# Esquematico.net
KiCad netlist of a schematic drawn in Altium Designer
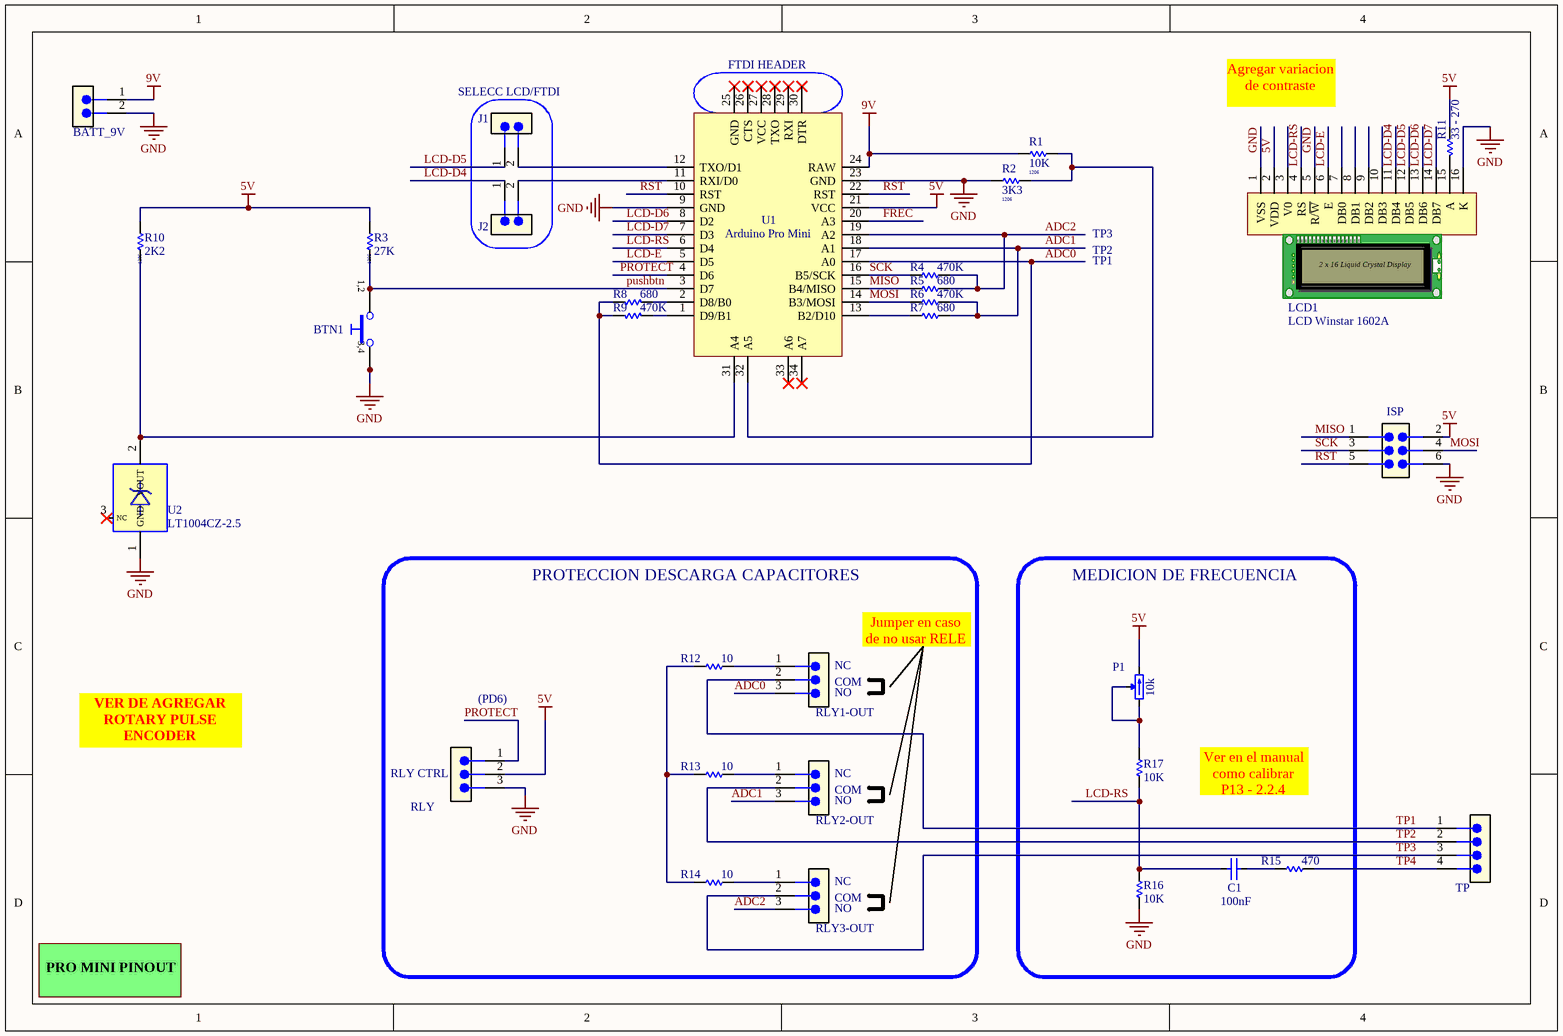
[diagram p0: Esquematico.SchDoc]

(export (version "E")
  (design (tool "Eeschema 10.0.6"))
  (components
    (comp (ref "BATT_9V")
      (value "M20-9 73 02 46")
      (footprint "HEADER2X1")
      (description "Header recto M 100 mils pitch 2x1")
      (fields (field (name "EM_MFR_PARTNUM") "NA") (field (name "MANUFACTURER") "Harwin"))
      (libsource (lib "") (part "HEADER 2X1_1"))
    )
    (comp (ref "BTN1")
      (value "Push Button")
      (footprint "PB_OMRON_B3F-1070")
      (description "Push-Button Switch SPDT")
      (fields
        (field (name "PART NUMBER") "PB_OMRON_B3F-1070")
        (field (name "MANUFACTURER") "OMRON")
        (field (name "AUTHOR") "CERN DEM JLC")
      )
      (libsource (lib "Schlib1") (part "SW TACT LONG 4Pin"))
    )
    (comp (ref "C1") (value "100nF") (footprint "1206 - CAP") (libsource (lib "Schlib1") (part "CAP_1206")))
    (comp (ref "ISP")
      (value "M20-9 72 03 46")
      (footprint "HEADER3X2")
      (description "Header recto M 100 mils pitch 3x2")
      (fields (field (name "EM_MFR_PARTNUM") "NA") (field (name "MANUFACTURER") "Harwin"))
      (libsource (lib "Schlib1") (part "HEADER 3X2"))
    )
    (comp (ref "J1")
      (value "M20-9 73 02 46")
      (footprint "HEADER2X1")
      (description "Header recto M 100 mils pitch 2x1")
      (fields (field (name "EM_MFR_PARTNUM") "NA") (field (name "MANUFACTURER") "Harwin"))
      (libsource (lib "") (part "HEADER 2X1_2"))
    )
    (comp (ref "J2")
      (value "M20-9 73 02 46")
      (footprint "HEADER2X1")
      (description "Header recto M 100 mils pitch 2x1")
      (fields (field (name "EM_MFR_PARTNUM") "NA") (field (name "MANUFACTURER") "Harwin"))
      (libsource (lib "Schlib1") (part "HEADER 2X1"))
    )
    (comp (ref "LCD1")
      (value "LCD Winstar 1602A")
      (footprint "LCD_1602A")
      (description "16x2 4-Bit Parallel LCD display HD44780 compatible")
      (libsource (lib "Schlib1") (part "LCD Winstar 1602A"))
    )
    (comp (ref "P1")
      (value "10k")
      (footprint "TRIM_BOURNS_3266W")
      (description "Trimming Pot THD")
      (fields
        (field (name "PART NUMBER") "TRIM_12T_10K_BOURNS_3266W-1-103LF")
        (field (name "POWER") "0.25W")
        (field (name "AUTHOR") "CERN DEM JLC")
      )
      (libsource (lib "Schlib1") (part "Trimming Pot THD"))
    )
    (comp (ref "R1")
      (value "10K")
      (footprint "1206 - RES")
      (fields (field (name "PACKAGE") "1206"))
      (libsource (lib "Schlib1") (part "RES_1206"))
    )
    (comp (ref "R2")
      (value "3K3")
      (footprint "1206 - RES")
      (fields (field (name "PACKAGE") "1206"))
      (libsource (lib "Schlib1") (part "RES_1206"))
    )
    (comp (ref "R3")
      (value "27K")
      (footprint "1206 - RES")
      (fields (field (name "PACKAGE") "1206"))
      (libsource (lib "Schlib1") (part "RES_1206"))
    )
    (comp (ref "R4") (value "470K") (footprint "1206 - RES") (libsource (lib "Schlib1") (part "RES_1206")))
    (comp (ref "R5") (value "680") (footprint "1206 - RES") (libsource (lib "Schlib1") (part "RES_1206")))
    (comp (ref "R6") (value "470K") (footprint "1206 - RES") (libsource (lib "Schlib1") (part "RES_1206")))
    (comp (ref "R7") (value "680") (footprint "1206 - RES") (libsource (lib "Schlib1") (part "RES_1206")))
    (comp (ref "R8") (value "680") (footprint "1206 - RES") (libsource (lib "Schlib1") (part "RES_1206")))
    (comp (ref "R9") (value "470K") (footprint "1206 - RES") (libsource (lib "Schlib1") (part "RES_1206")))
    (comp (ref "R10")
      (value "2K2")
      (footprint "1206 - RES")
      (fields (field (name "PACKAGE") "1206"))
      (libsource (lib "Schlib1") (part "RES_1206"))
    )
    (comp (ref "R11")
      (value "33 - 270")
      (footprint "1206 - RES")
      (libsource (lib "Schlib1") (part "RES_1206"))
    )
    (comp (ref "R12") (value "10") (footprint "1206 - RES") (libsource (lib "Schlib1") (part "RES_1206")))
    (comp (ref "R13") (value "10") (footprint "1206 - RES") (libsource (lib "Schlib1") (part "RES_1206")))
    (comp (ref "R14") (value "10") (footprint "1206 - RES") (libsource (lib "Schlib1") (part "RES_1206")))
    (comp (ref "R15") (value "470") (footprint "1206 - RES") (libsource (lib "Schlib1") (part "RES_1206")))
    (comp (ref "R16") (value "10K") (footprint "1206 - RES") (libsource (lib "Schlib1") (part "RES_1206")))
    (comp (ref "R17") (value "10K") (footprint "1206 - RES") (libsource (lib "Schlib1") (part "RES_1206")))
    (comp (ref "RLY") (value "HEADER 3X1") (footprint "HEADER3X1") (libsource (lib "") (part "HEADER 3X1_1")))
    (comp (ref "RLY1-OUT")
      (value "HEADER 3X1")
      (footprint "HEADER3X1")
      (libsource (lib "Schlib1") (part "HEADER 3X1"))
    )
    (comp (ref "RLY2-OUT")
      (value "HEADER 3X1")
      (footprint "HEADER3X1")
      (libsource (lib "Schlib1") (part "HEADER 3X1"))
    )
    (comp (ref "RLY3-OUT")
      (value "HEADER 3X1")
      (footprint "HEADER3X1")
      (libsource (lib "Schlib1") (part "HEADER 3X1"))
    )
    (comp (ref "TP")
      (value "M20-9 73 04 46")
      (footprint "HEADER4X1")
      (description "Header recto M 100 mils pitch 4x1")
      (fields (field (name "EM_MFR_PARTNUM") "NA") (field (name "MANUFACTURER") "Harwin"))
      (libsource (lib "Schlib1") (part "HEADER 4X1"))
    )
    (comp (ref "U1")
      (value "Arduino Pro Mini")
      (footprint "Arduino Pro Mini")
      (libsource (lib "Schlib1") (part "Arduino Pro Mini"))
    )
    (comp (ref "U2")
      (value "LT1004CZ-2.5")
      (footprint "TO-92")
      (description "VREF SHUNT 2.5V TO-92")
      (fields (field (name "MANUFACTURER") "Analog Devices"))
      (libsource (lib "Schlib1") (part "LT1004CZ-2.5"))
    )
  )
  (nets
    (net (code "1") (name "/ADC0") (class "Default")
      (node (ref "R8") (pin "1") (pinfunction "1_1") (pintype "passive"))
      (node (ref "R9") (pin "1") (pinfunction "1_1") (pintype "passive"))
      (node (ref "RLY1-OUT") (pin "3") (pinfunction "3_3") (pintype "passive"))
      (node (ref "U1") (pin "17") (pinfunction "A0_17") (pintype "passive"))
    )
    (net (code "2") (name "/ADC1") (class "Default")
      (node (ref "R6") (pin "1") (pinfunction "1_1") (pintype "passive"))
      (node (ref "R7") (pin "1") (pinfunction "1_1") (pintype "passive"))
      (node (ref "RLY2-OUT") (pin "3") (pinfunction "3_3") (pintype "passive"))
      (node (ref "U1") (pin "18") (pinfunction "A1_18") (pintype "passive"))
    )
    (net (code "3") (name "/ADC2") (class "Default")
      (node (ref "R4") (pin "1") (pinfunction "1_1") (pintype "passive"))
      (node (ref "R5") (pin "1") (pinfunction "1_1") (pintype "passive"))
      (node (ref "RLY3-OUT") (pin "3") (pinfunction "3_3") (pintype "passive"))
      (node (ref "U1") (pin "19") (pinfunction "A2_19") (pintype "passive"))
    )
    (net (code "4") (name "/FREC") (class "Default")
      (node (ref "U1") (pin "20") (pinfunction "A3_20") (pintype "passive"))
    )
    (net (code "5") (name "/LCD-D4") (class "Default")
      (node (ref "J2") (pin "1") (pinfunction "1_1") (pintype "passive"))
      (node (ref "LCD1") (pin "11") (pinfunction "DB4_11") (pintype "passive"))
    )
    (net (code "6") (name "/LCD-D5") (class "Default")
      (node (ref "J1") (pin "1") (pinfunction "1_1") (pintype "passive"))
      (node (ref "LCD1") (pin "12") (pinfunction "DB5_12") (pintype "passive"))
    )
    (net (code "7") (name "/LCD-D6") (class "Default")
      (node (ref "LCD1") (pin "13") (pinfunction "DB6_13") (pintype "passive"))
      (node (ref "U1") (pin "8") (pinfunction "D2_8") (pintype "passive"))
    )
    (net (code "8") (name "/LCD-D7") (class "Default")
      (node (ref "LCD1") (pin "14") (pinfunction "DB7_14") (pintype "passive"))
      (node (ref "U1") (pin "7") (pinfunction "D3_7") (pintype "passive"))
    )
    (net (code "9") (name "/LCD-E") (class "Default")
      (node (ref "LCD1") (pin "6") (pinfunction "E_6") (pintype "passive"))
      (node (ref "U1") (pin "5") (pinfunction "D5_5") (pintype "passive"))
    )
    (net (code "10") (name "/LCD-RS") (class "Default")
      (node (ref "C1") (pin "1") (pinfunction "1_1") (pintype "passive"))
      (node (ref "LCD1") (pin "4") (pinfunction "RS_4") (pintype "passive"))
      (node (ref "R16") (pin "2") (pinfunction "2_2") (pintype "passive"))
      (node (ref "R17") (pin "1") (pinfunction "1_1") (pintype "passive"))
      (node (ref "U1") (pin "6") (pinfunction "D4_6") (pintype "passive"))
    )
    (net (code "11") (name "/MISO") (class "Default")
      (node (ref "ISP") (pin "1") (pinfunction "1_1") (pintype "passive"))
      (node (ref "R5") (pin "2") (pinfunction "2_2") (pintype "passive"))
      (node (ref "U1") (pin "15") (pinfunction "B4/MISO_15") (pintype "passive"))
    )
    (net (code "12") (name "/MOSI") (class "Default")
      (node (ref "ISP") (pin "4") (pinfunction "4_4") (pintype "passive"))
      (node (ref "R6") (pin "2") (pinfunction "2_2") (pintype "passive"))
      (node (ref "U1") (pin "14") (pinfunction "B3/MOSI_14") (pintype "passive"))
    )
    (net (code "13") (name "/PROTECT") (class "Default")
      (node (ref "RLY") (pin "1") (pinfunction "1_1") (pintype "passive"))
      (node (ref "U1") (pin "4") (pinfunction "D6_4") (pintype "passive"))
    )
    (net (code "14") (name "/RST") (class "Default")
      (node (ref "ISP") (pin "5") (pinfunction "5_5") (pintype "passive"))
      (node (ref "U1") (pin "10") (pinfunction "RST_10") (pintype "passive"))
      (node (ref "U1") (pin "22") (pinfunction "RST_22") (pintype "passive"))
    )
    (net (code "15") (name "/SCK") (class "Default")
      (node (ref "ISP") (pin "3") (pinfunction "3_3") (pintype "passive"))
      (node (ref "R4") (pin "2") (pinfunction "2_2") (pintype "passive"))
      (node (ref "U1") (pin "16") (pinfunction "B5/SCK_16") (pintype "passive"))
    )
    (net (code "16") (name "/TP1") (class "Default")
      (node (ref "RLY1-OUT") (pin "2") (pinfunction "2_2") (pintype "passive"))
      (node (ref "TP") (pin "1") (pinfunction "1_1") (pintype "passive"))
    )
    (net (code "17") (name "/TP2") (class "Default")
      (node (ref "RLY2-OUT") (pin "2") (pinfunction "2_2") (pintype "passive"))
      (node (ref "TP") (pin "2") (pinfunction "2_2") (pintype "passive"))
    )
    (net (code "18") (name "/TP3") (class "Default")
      (node (ref "RLY3-OUT") (pin "2") (pinfunction "2_2") (pintype "passive"))
      (node (ref "TP") (pin "3") (pinfunction "3_3") (pintype "passive"))
    )
    (net (code "19") (name "/TP4") (class "Default")
      (node (ref "R15") (pin "1") (pinfunction "1_1") (pintype "passive"))
      (node (ref "TP") (pin "4") (pinfunction "4_4") (pintype "passive"))
    )
    (net (code "20") (name "/pushbtn") (class "Default")
      (node (ref "BTN1") (pin "1") (pinfunction "1_1") (pintype "passive"))
      (node (ref "BTN1") (pin "2") (pinfunction "2_2") (pintype "passive"))
      (node (ref "R3") (pin "1") (pinfunction "1_1") (pintype "passive"))
      (node (ref "U1") (pin "3") (pinfunction "D7_3") (pintype "passive"))
    )
    (net (code "21") (name "5V") (class "Default")
      (node (ref "ISP") (pin "2") (pinfunction "2_2") (pintype "passive"))
      (node (ref "LCD1") (pin "2") (pinfunction "VDD_2") (pintype "passive"))
      (node (ref "P1") (pin "3") (pinfunction "CW_3") (pintype "passive"))
      (node (ref "R10") (pin "2") (pinfunction "2_2") (pintype "passive"))
      (node (ref "R11") (pin "2") (pinfunction "2_2") (pintype "passive"))
      (node (ref "R3") (pin "2") (pinfunction "2_2") (pintype "passive"))
      (node (ref "RLY") (pin "2") (pinfunction "2_2") (pintype "passive"))
      (node (ref "U1") (pin "21") (pinfunction "VCC_21") (pintype "passive"))
    )
    (net (code "22") (name "9V") (class "Default")
      (node (ref "BATT_9V") (pin "1") (pinfunction "1_1") (pintype "passive"))
      (node (ref "R1") (pin "2") (pinfunction "2_2") (pintype "passive"))
      (node (ref "U1") (pin "24") (pinfunction "RAW_24") (pintype "passive"))
    )
    (net (code "23") (name "GND") (class "Default")
      (node (ref "BATT_9V") (pin "2") (pinfunction "2_2") (pintype "passive"))
      (node (ref "BTN1") (pin "3") (pinfunction "3_3") (pintype "passive"))
      (node (ref "BTN1") (pin "4") (pinfunction "4_4") (pintype "passive"))
      (node (ref "ISP") (pin "6") (pinfunction "6_6") (pintype "passive"))
      (node (ref "LCD1") (pin "1") (pinfunction "VSS_1") (pintype "passive"))
      (node (ref "LCD1") (pin "16") (pinfunction "K_16") (pintype "passive"))
      (node (ref "LCD1") (pin "5") (pinfunction "R/~{W}_5") (pintype "passive"))
      (node (ref "R16") (pin "1") (pinfunction "1_1") (pintype "passive"))
      (node (ref "R2") (pin "2") (pinfunction "2_2") (pintype "passive"))
      (node (ref "RLY") (pin "3") (pinfunction "3_3") (pintype "passive"))
      (node (ref "U1") (pin "23") (pinfunction "GND_23") (pintype "passive"))
      (node (ref "U1") (pin "9") (pinfunction "GND_9") (pintype "passive"))
      (node (ref "U2") (pin "1") (pinfunction "GND_1") (pintype "passive"))
    )
    (net (code "24") (name "Net-(C1-Pad2)") (class "Default")
      (node (ref "C1") (pin "2") (pinfunction "2_2") (pintype "passive"))
      (node (ref "R15") (pin "2") (pinfunction "2_2") (pintype "passive"))
    )
    (net (code "25") (name "Net-(LCD1-A)") (class "Default")
      (node (ref "LCD1") (pin "15") (pinfunction "A_15") (pintype "passive"))
      (node (ref "R11") (pin "1") (pinfunction "1_1") (pintype "passive"))
    )
    (net (code "26") (name "Net-(P1-CCW)") (class "Default")
      (node (ref "P1") (pin "1") (pinfunction "CCW_1") (pintype "passive"))
      (node (ref "P1") (pin "2") (pinfunction "W_2") (pintype "passive"))
      (node (ref "R17") (pin "2") (pinfunction "2_2") (pintype "passive"))
    )
    (net (code "27") (name "Net-(R12-Pad1)") (class "Default")
      (node (ref "R12") (pin "1") (pinfunction "1_1") (pintype "passive"))
      (node (ref "RLY1-OUT") (pin "1") (pinfunction "1_1") (pintype "passive"))
    )
    (net (code "28") (name "Net-(R12-Pad2)") (class "Default")
      (node (ref "R12") (pin "2") (pinfunction "2_2") (pintype "passive"))
      (node (ref "R13") (pin "2") (pinfunction "2_2") (pintype "passive"))
      (node (ref "R14") (pin "2") (pinfunction "2_2") (pintype "passive"))
    )
    (net (code "29") (name "Net-(R13-Pad1)") (class "Default")
      (node (ref "R13") (pin "1") (pinfunction "1_1") (pintype "passive"))
      (node (ref "RLY2-OUT") (pin "1") (pinfunction "1_1") (pintype "passive"))
    )
    (net (code "30") (name "Net-(R14-Pad1)") (class "Default")
      (node (ref "R14") (pin "1") (pinfunction "1_1") (pintype "passive"))
      (node (ref "RLY3-OUT") (pin "1") (pinfunction "1_1") (pintype "passive"))
    )
    (net (code "31") (name "Net-(U1-A4)") (class "Default")
      (node (ref "R10") (pin "1") (pinfunction "1_1") (pintype "passive"))
      (node (ref "U1") (pin "31") (pinfunction "A4_31") (pintype "passive"))
      (node (ref "U2") (pin "2") (pinfunction "VOUT_2") (pintype "passive"))
    )
    (net (code "32") (name "Net-(U1-A5)") (class "Default")
      (node (ref "R1") (pin "1") (pinfunction "1_1") (pintype "passive"))
      (node (ref "R2") (pin "1") (pinfunction "1_1") (pintype "passive"))
      (node (ref "U1") (pin "32") (pinfunction "A5_32") (pintype "passive"))
    )
    (net (code "33") (name "Net-(U1-B2{slash}D10)") (class "Default")
      (node (ref "R7") (pin "2") (pinfunction "2_2") (pintype "passive"))
      (node (ref "U1") (pin "13") (pinfunction "B2/D10_13") (pintype "passive"))
    )
    (net (code "34") (name "Net-(U1-D8{slash}B0)") (class "Default")
      (node (ref "R8") (pin "2") (pinfunction "2_2") (pintype "passive"))
      (node (ref "U1") (pin "2") (pinfunction "D8/B0_2") (pintype "passive"))
    )
    (net (code "35") (name "Net-(U1-D9{slash}B1)") (class "Default")
      (node (ref "R9") (pin "2") (pinfunction "2_2") (pintype "passive"))
      (node (ref "U1") (pin "1") (pinfunction "D9/B1_1") (pintype "passive"))
    )
    (net (code "36") (name "Net-(U1-RXI{slash}D0)") (class "Default")
      (node (ref "J2") (pin "2") (pinfunction "2_2") (pintype "passive"))
      (node (ref "U1") (pin "11") (pinfunction "RXI/D0_11") (pintype "passive"))
    )
    (net (code "37") (name "Net-(U1-TXO{slash}D1)") (class "Default")
      (node (ref "J1") (pin "2") (pinfunction "2_2") (pintype "passive"))
      (node (ref "U1") (pin "12") (pinfunction "TXO/D1_12") (pintype "passive"))
    )
    (net (code "38") (name "unconnected-(LCD1-DB0-Pad7)") (class "Default")
      (node (ref "LCD1") (pin "7") (pinfunction "DB0_7") (pintype "passive"))
    )
    (net (code "39") (name "unconnected-(LCD1-DB1-Pad8)") (class "Default")
      (node (ref "LCD1") (pin "8") (pinfunction "DB1_8") (pintype "passive"))
    )
    (net (code "40") (name "unconnected-(LCD1-DB2-Pad9)") (class "Default")
      (node (ref "LCD1") (pin "9") (pinfunction "DB2_9") (pintype "passive"))
    )
    (net (code "41") (name "unconnected-(LCD1-DB3-Pad10)") (class "Default")
      (node (ref "LCD1") (pin "10") (pinfunction "DB3_10") (pintype "passive"))
    )
    (net (code "42") (name "unconnected-(LCD1-V0-Pad3)") (class "Default")
      (node (ref "LCD1") (pin "3") (pinfunction "V0_3") (pintype "passive"))
    )
    (net (code "43") (name "unconnected-(U1-A6-Pad33)") (class "Default")
      (node (ref "U1") (pin "33") (pinfunction "A6_33") (pintype "passive+no_connect"))
    )
    (net (code "44") (name "unconnected-(U1-A7-Pad34)") (class "Default")
      (node (ref "U1") (pin "34") (pinfunction "A7_34") (pintype "passive+no_connect"))
    )
    (net (code "45") (name "unconnected-(U1-CTS-Pad26)") (class "Default")
      (node (ref "U1") (pin "26") (pinfunction "CTS_26") (pintype "passive+no_connect"))
    )
    (net (code "46") (name "unconnected-(U1-DTR-Pad30)") (class "Default")
      (node (ref "U1") (pin "30") (pinfunction "DTR_30") (pintype "passive+no_connect"))
    )
    (net (code "47") (name "unconnected-(U1-GND-Pad25)") (class "Default")
      (node (ref "U1") (pin "25") (pinfunction "GND_25") (pintype "passive+no_connect"))
    )
    (net (code "48") (name "unconnected-(U1-RXI-Pad29)") (class "Default")
      (node (ref "U1") (pin "29") (pinfunction "RXI_29") (pintype "passive+no_connect"))
    )
    (net (code "49") (name "unconnected-(U1-TXO-Pad28)") (class "Default")
      (node (ref "U1") (pin "28") (pinfunction "TXO_28") (pintype "passive+no_connect"))
    )
    (net (code "50") (name "unconnected-(U1-VCC-Pad27)") (class "Default")
      (node (ref "U1") (pin "27") (pinfunction "VCC_27") (pintype "passive+no_connect"))
    )
    (net (code "51") (name "unconnected-(U2-NC-Pad3)") (class "Default")
      (node (ref "U2") (pin "3") (pinfunction "NC_3") (pintype "passive+no_connect"))
    )
  )
)
